# design.net
KiCad netlist of a schematic drawn in Altium Designer
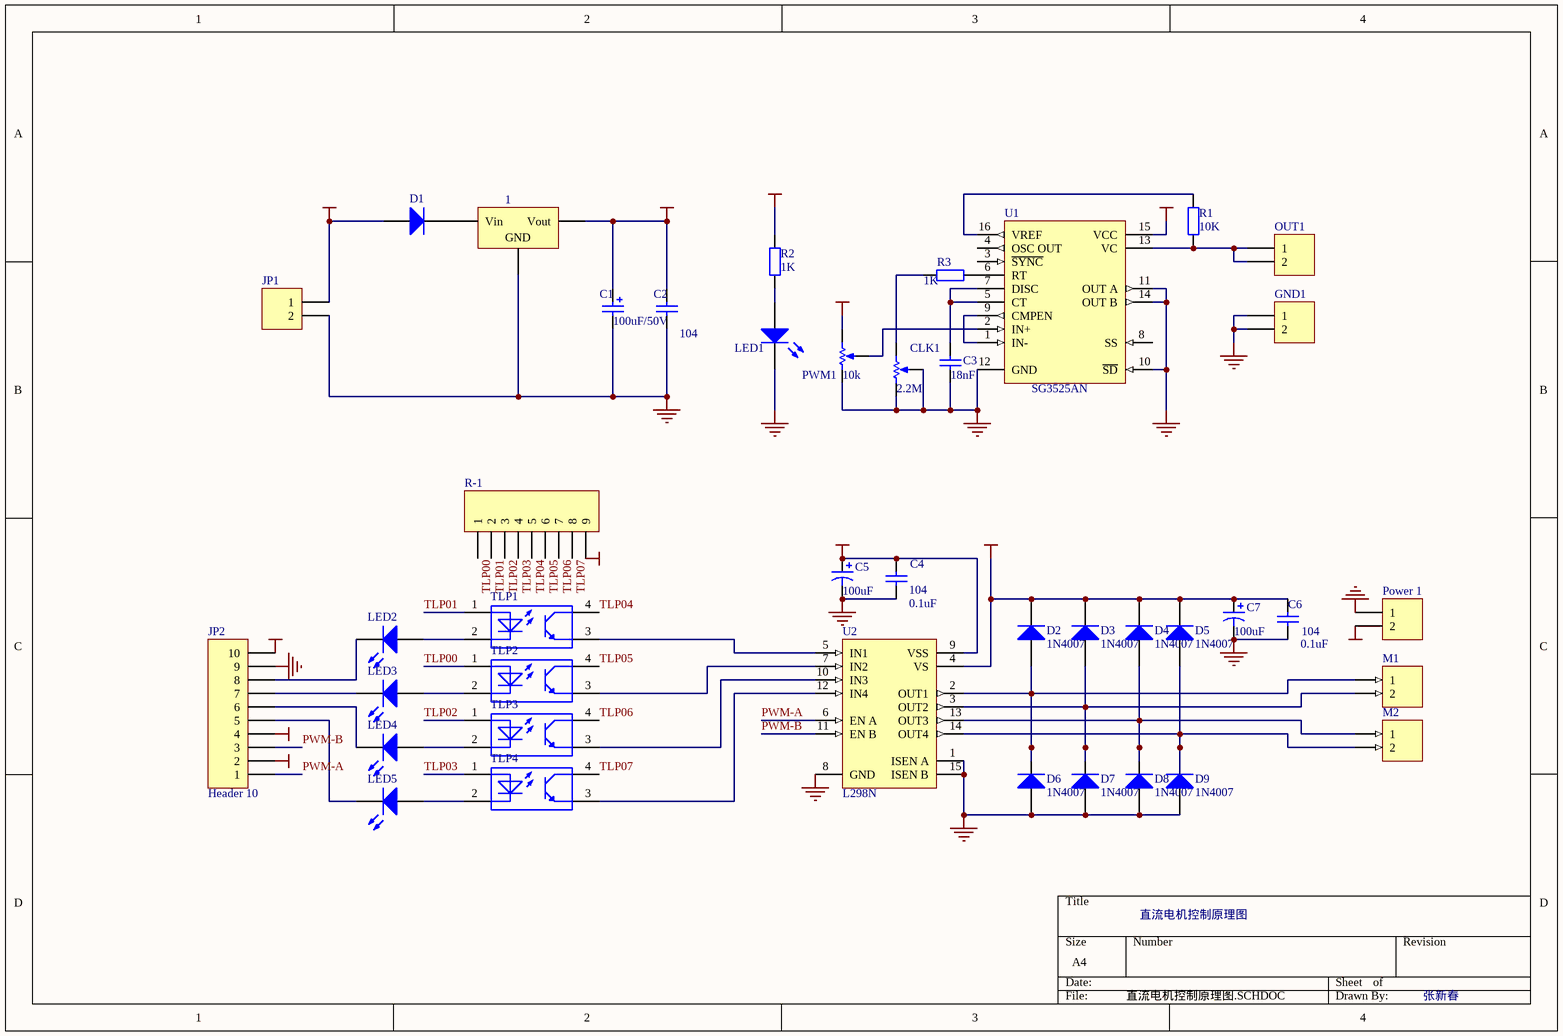
[diagram p0: 直流电机控制原理图.SCHDOC]

(export (version "E")
  (design (tool "Eeschema 10.0.6"))
  (components
    (comp (ref "1")
      (value "SDWYG")
      (footprint "WYG")
      (description "三端稳压器")
      (fields (field (name "PUBLISHER") "Altium Limited"))
      (libsource (lib "zxcourhc") (part "SDWYG"))
    )
    (comp (ref "C1")
      (value "100uF/50V")
      (footprint "C-DJ-6")
      (description "电解电容")
      (fields (field (name "Comment") "DJDR") (field (name "PUBLISHER") "Altium Limited"))
      (libsource (lib "zxcourhc") (part "DJDR"))
    )
    (comp (ref "C2")
      (value "104")
      (footprint "CPDR")
      (description "瓷片电容")
      (fields (field (name "Comment") "CPDR") (field (name "PUBLISHER") "Altium Limited"))
      (libsource (lib "zxcourhc") (part "CPDR"))
    )
    (comp (ref "C3")
      (value "18nF")
      (footprint "CPDR")
      (description "Capacitor (Semiconductor SIM Model)")
      (fields (field (name "Comment") "Cap Semi") (field (name "PUBLISHER") "Altium Limited"))
      (libsource (lib "Miscellaneous Devices") (part "Cap Semi"))
    )
    (comp (ref "C4")
      (value "104")
      (footprint "BAT-2")
      (description "Capacitor")
      (fields (field (name "ALTIUM_VALUE") "0.1uF") (field (name "PUBLISHER") "Altium Limited"))
      (libsource (lib "Miscellaneous Devices") (part "Cap"))
    )
    (comp (ref "C5")
      (value "100uF")
      (footprint "CAPPR2-5x6.8")
      (description "Polarized Capacitor (Surface Mount)")
      (fields (field (name "PUBLISHER") "Altium Limited"))
      (libsource (lib "Miscellaneous Devices") (part "Cap Pol3"))
    )
    (comp (ref "C6")
      (value "104")
      (footprint "BAT-2")
      (description "Capacitor")
      (fields (field (name "ALTIUM_VALUE") "0.1uF") (field (name "PUBLISHER") "Altium Limited"))
      (libsource (lib "Miscellaneous Devices") (part "Cap"))
    )
    (comp (ref "C7")
      (value "100uF")
      (footprint "CAPPR2-5x6.8")
      (description "Polarized Capacitor (Surface Mount)")
      (fields (field (name "PUBLISHER") "Altium Limited"))
      (libsource (lib "Miscellaneous Devices") (part "Cap Pol3"))
    )
    (comp (ref "CLK1")
      (value "2.2M")
      (footprint "SIP3-D")
      (description "Potentiometer")
      (fields (field (name "Comment") "RPot") (field (name "PUBLISHER") "Altium Limited"))
      (libsource (lib "Miscellaneous Devices") (part "RPot"))
    )
    (comp (ref "D1")
      (value "Diode 1N4007")
      (footprint "D-ZL-10")
      (description "1 Amp General Purpose Rectifier")
      (fields (field (name "PUBLISHER") "Altium Limited"))
      (libsource (lib "Miscellaneous Devices") (part "Diode 1N4007"))
    )
    (comp (ref "D2")
      (value "1N4007")
      (footprint "DIO7.8-4.6x2")
      (description "1 Amp General Purpose Rectifier")
      (fields (field (name "PUBLISHER") "Altium Limited"))
      (libsource (lib "Miscellaneous Devices") (part "Diode 1N4007"))
    )
    (comp (ref "D3")
      (value "1N4007")
      (footprint "DIO7.8-4.6x2")
      (description "1 Amp General Purpose Rectifier")
      (fields (field (name "PUBLISHER") "Altium Limited"))
      (libsource (lib "Miscellaneous Devices") (part "Diode 1N4007"))
    )
    (comp (ref "D4")
      (value "1N4007")
      (footprint "DIO7.8-4.6x2")
      (description "1 Amp General Purpose Rectifier")
      (fields (field (name "PUBLISHER") "Altium Limited"))
      (libsource (lib "Miscellaneous Devices") (part "Diode 1N4007"))
    )
    (comp (ref "D5")
      (value "1N4007")
      (footprint "DIO7.8-4.6x2")
      (description "1 Amp General Purpose Rectifier")
      (fields (field (name "PUBLISHER") "Altium Limited"))
      (libsource (lib "Miscellaneous Devices") (part "Diode 1N4007"))
    )
    (comp (ref "D6")
      (value "1N4007")
      (footprint "DIO7.8-4.6x2")
      (description "1 Amp General Purpose Rectifier")
      (fields (field (name "PUBLISHER") "Altium Limited"))
      (libsource (lib "Miscellaneous Devices") (part "Diode 1N4007"))
    )
    (comp (ref "D7")
      (value "1N4007")
      (footprint "DIO7.8-4.6x2")
      (description "1 Amp General Purpose Rectifier")
      (fields (field (name "PUBLISHER") "Altium Limited"))
      (libsource (lib "Miscellaneous Devices") (part "Diode 1N4007"))
    )
    (comp (ref "D8")
      (value "1N4007")
      (footprint "DIO7.8-4.6x2")
      (description "1 Amp General Purpose Rectifier")
      (fields (field (name "PUBLISHER") "Altium Limited"))
      (libsource (lib "Miscellaneous Devices") (part "Diode 1N4007"))
    )
    (comp (ref "D9")
      (value "1N4007")
      (footprint "DIO7.8-4.6x2")
      (description "1 Amp General Purpose Rectifier")
      (fields (field (name "PUBLISHER") "Altium Limited"))
      (libsource (lib "Miscellaneous Devices") (part "Diode 1N4007"))
    )
    (comp (ref "GND1")
      (value "Header 2")
      (footprint "HDR1X2")
      (description "Header, 2-Pin")
      (fields (field (name "PUBLISHER") "Altium Limited"))
      (libsource (lib "Miscellaneous Connectors") (part "Header 2"))
    )
    (comp (ref "JP1")
      (value "PZ_2")
      (footprint "zxcourhc:JK128_2")
      (description "排针——2")
      (fields (field (name "PUBLISHER") "Altium Limited"))
      (libsource (lib "zxcourhc") (part "PZ_2"))
    )
    (comp (ref "JP2")
      (value "Header 10")
      (footprint "HDR1X10")
      (description "Header, 10-Pin")
      (fields (field (name "PUBLISHER") "Altium Limited"))
      (libsource (lib "Miscellaneous Connectors") (part "Header 10"))
    )
    (comp (ref "LED1")
      (value "LED2")
      (footprint "LED_D")
      (description "Typical RED, GREEN, YELLOW, AMBER GaAs LED")
      (fields (field (name "PUBLISHER") "Altium Limited"))
      (libsource (lib "Miscellaneous Devices") (part "LED2"))
    )
    (comp (ref "LED2")
      (value "~")
      (footprint "HDR1X2")
      (description "Typical BLUE SiC LED")
      (fields (field (name "PUBLISHER") "Altium Limited"))
      (libsource (lib "Miscellaneous Devices") (part "LED3"))
    )
    (comp (ref "LED3")
      (value "~")
      (footprint "HDR1X2")
      (description "Typical BLUE SiC LED")
      (fields (field (name "PUBLISHER") "Altium Limited"))
      (libsource (lib "Miscellaneous Devices") (part "LED3"))
    )
    (comp (ref "LED4")
      (value "~")
      (footprint "HDR1X2")
      (description "Typical BLUE SiC LED")
      (fields (field (name "PUBLISHER") "Altium Limited"))
      (libsource (lib "Miscellaneous Devices") (part "LED3"))
    )
    (comp (ref "LED5")
      (value "~")
      (footprint "HDR1X2")
      (description "Typical BLUE SiC LED")
      (fields (field (name "PUBLISHER") "Altium Limited"))
      (libsource (lib "Miscellaneous Devices") (part "LED3"))
    )
    (comp (ref "M1")
      (value "~")
      (footprint "JK128")
      (description "Header, 2-Pin")
      (fields (field (name "PUBLISHER") "Altium Limited"))
      (libsource (lib "Miscellaneous Connectors") (part "MHDR1X2"))
    )
    (comp (ref "M2")
      (value "~")
      (footprint "JK128")
      (description "Header, 2-Pin")
      (fields (field (name "PUBLISHER") "Altium Limited"))
      (libsource (lib "Miscellaneous Connectors") (part "MHDR1X2"))
    )
    (comp (ref "OUT1")
      (value "Header 2")
      (footprint "HDR1X2")
      (description "Header, 2-Pin")
      (fields (field (name "PUBLISHER") "Altium Limited"))
      (libsource (lib "Miscellaneous Connectors") (part "Header 2"))
    )
    (comp (ref "Power 1")
      (value "~")
      (footprint "JK128")
      (description "Header, 2-Pin")
      (fields (field (name "PUBLISHER") "Altium Limited"))
      (libsource (lib "Miscellaneous Connectors") (part "MHDR1X2"))
    )
    (comp (ref "PWM1")
      (value "10k")
      (footprint "SIP3-D")
      (description "Potentiometer")
      (fields (field (name "Comment") "RPot") (field (name "PUBLISHER") "Altium Limited"))
      (libsource (lib "Miscellaneous Devices") (part "RPot"))
    )
    (comp (ref "R-1")
      (value "~")
      (footprint "HDR1X9")
      (description "Header, 9-Pin")
      (fields (field (name "PUBLISHER") "Altium Limited"))
      (libsource (lib "Miscellaneous Connectors") (part "Header 9"))
    )
    (comp (ref "R1")
      (value "10K")
      (footprint "AXIAL-0.4")
      (description "Resistor")
      (fields (field (name "Comment") "Res2") (field (name "PUBLISHER") "Altium Limited"))
      (libsource (lib "") (part "Res2_1"))
    )
    (comp (ref "R2")
      (value "1K")
      (footprint "AXIAL-0.4")
      (description "Resistor")
      (fields (field (name "Comment") "Res2") (field (name "PUBLISHER") "Altium Limited"))
      (libsource (lib "") (part "Res2_2"))
    )
    (comp (ref "R3")
      (value "1K")
      (footprint "AXIAL-0.4")
      (description "Resistor")
      (fields (field (name "Comment") "Res2") (field (name "PUBLISHER") "Altium Limited"))
      (libsource (lib "Miscellaneous Devices") (part "Res2"))
    )
    (comp (ref "TLP1") (value "~") (footprint "DIP4") (libsource (lib "MyInt_Lib") (part "TLP521-1")))
    (comp (ref "TLP2") (value "~") (footprint "DIP4") (libsource (lib "MyInt_Lib") (part "TLP521-1")))
    (comp (ref "TLP3") (value "~") (footprint "DIP4") (libsource (lib "MyInt_Lib") (part "TLP521-1")))
    (comp (ref "TLP4") (value "~") (footprint "DIP4") (libsource (lib "MyInt_Lib") (part "TLP521-1")))
    (comp (ref "U1")
      (value "SG3525AN")
      (footprint "DIP16")
      (description "Pulse Width Modulator Control Circuit")
      (fields (field (name "PUBLISHER") "Altium Limited"))
      (libsource (lib "ON Semi Power Mgt SMPS Controller") (part "SG3525AN"))
    )
    (comp (ref "U2")
      (value "L298N")
      (footprint "DFM-T15/X1.6V")
      (description "Dual Full Bridge Driver")
      (fields (field (name "PUBLISHER") "Altium Limited"))
      (libsource (lib "ST Interface DC Motor Controller") (part "L298N"))
    )
  )
  (nets
    (net (code "1") (name "+5V") (class "Default")
      (node (ref "C4") (pin "2") (pinfunction "2_2") (pintype "passive"))
      (node (ref "C5") (pin "1") (pinfunction "1_1") (pintype "passive"))
      (node (ref "JP2") (pin "10") (pinfunction "10_10") (pintype "passive"))
      (node (ref "JP2") (pin "2") (pinfunction "2_2") (pintype "passive"))
      (node (ref "JP2") (pin "4") (pinfunction "4_4") (pintype "passive"))
      (node (ref "R-1") (pin "9") (pinfunction "9_9") (pintype "passive"))
      (node (ref "U2") (pin "9") (pinfunction "VSS_9") (pintype "power_in"))
    )
    (net (code "2") (name "+12V") (class "Default")
      (node (ref "C6") (pin "2") (pinfunction "2_2") (pintype "passive"))
      (node (ref "C7") (pin "1") (pinfunction "1_1") (pintype "passive"))
      (node (ref "D2") (pin "2") (pinfunction "K_2") (pintype "passive"))
      (node (ref "D3") (pin "2") (pinfunction "K_2") (pintype "passive"))
      (node (ref "D4") (pin "2") (pinfunction "K_2") (pintype "passive"))
      (node (ref "D5") (pin "2") (pinfunction "K_2") (pintype "passive"))
      (node (ref "Power 1") (pin "2") (pinfunction "2_2") (pintype "input"))
      (node (ref "U2") (pin "4") (pinfunction "VS_4") (pintype "power_in"))
    )
    (net (code "3") (name "/PWM-A") (class "Default")
      (node (ref "JP2") (pin "1") (pinfunction "1_1") (pintype "passive"))
      (node (ref "U2") (pin "6") (pinfunction "EN_A_6") (pintype "input"))
    )
    (net (code "4") (name "/PWM-B") (class "Default")
      (node (ref "JP2") (pin "3") (pinfunction "3_3") (pintype "passive"))
      (node (ref "U2") (pin "11") (pinfunction "EN_B_11") (pintype "input"))
    )
    (net (code "5") (name "/TLP00") (class "Default")
      (node (ref "R-1") (pin "1") (pinfunction "1_1") (pintype "passive"))
      (node (ref "TLP2") (pin "1") (pinfunction "1_1") (pintype "passive"))
    )
    (net (code "6") (name "/TLP01") (class "Default")
      (node (ref "R-1") (pin "2") (pinfunction "2_2") (pintype "passive"))
      (node (ref "TLP1") (pin "1") (pinfunction "1_1") (pintype "passive"))
    )
    (net (code "7") (name "/TLP02") (class "Default")
      (node (ref "R-1") (pin "3") (pinfunction "3_3") (pintype "passive"))
      (node (ref "TLP3") (pin "1") (pinfunction "1_1") (pintype "passive"))
    )
    (net (code "8") (name "/TLP03") (class "Default")
      (node (ref "R-1") (pin "4") (pinfunction "4_4") (pintype "passive"))
      (node (ref "TLP4") (pin "1") (pinfunction "1_1") (pintype "passive"))
    )
    (net (code "9") (name "/TLP04") (class "Default")
      (node (ref "R-1") (pin "5") (pinfunction "5_5") (pintype "passive"))
      (node (ref "TLP1") (pin "4") (pinfunction "4_4") (pintype "passive"))
    )
    (net (code "10") (name "/TLP05") (class "Default")
      (node (ref "R-1") (pin "6") (pinfunction "6_6") (pintype "passive"))
      (node (ref "TLP2") (pin "4") (pinfunction "4_4") (pintype "passive"))
    )
    (net (code "11") (name "/TLP06") (class "Default")
      (node (ref "R-1") (pin "7") (pinfunction "7_7") (pintype "passive"))
      (node (ref "TLP3") (pin "4") (pinfunction "4_4") (pintype "passive"))
    )
    (net (code "12") (name "/TLP07") (class "Default")
      (node (ref "R-1") (pin "8") (pinfunction "8_8") (pintype "passive"))
      (node (ref "TLP4") (pin "4") (pinfunction "4_4") (pintype "passive"))
    )
    (net (code "13") (name "GND") (class "Default")
      (node (ref "1") (pin "3") (pinfunction "GND_3") (pintype "passive"))
      (node (ref "C1") (pin "2") (pinfunction "2_2") (pintype "passive"))
      (node (ref "C2") (pin "1") (pinfunction "1_1") (pintype "passive"))
      (node (ref "C3") (pin "2") (pinfunction "2_2") (pintype "passive"))
      (node (ref "C4") (pin "1") (pinfunction "1_1") (pintype "passive"))
      (node (ref "C5") (pin "2") (pinfunction "2_2") (pintype "passive"))
      (node (ref "CLK1") (pin "1") (pinfunction "TOP_1") (pintype "passive"))
      (node (ref "CLK1") (pin "3") (pinfunction "TAP_3") (pintype "passive"))
      (node (ref "GND1") (pin "1") (pinfunction "1_1") (pintype "passive"))
      (node (ref "GND1") (pin "2") (pinfunction "2_2") (pintype "passive"))
      (node (ref "JP1") (pin "2") (pinfunction "2_2") (pintype "passive"))
      (node (ref "JP2") (pin "9") (pinfunction "9_9") (pintype "passive"))
      (node (ref "LED1") (pin "2") (pinfunction "K_2") (pintype "passive"))
      (node (ref "PWM1") (pin "1") (pinfunction "TOP_1") (pintype "passive"))
      (node (ref "U1") (pin "10") (pinfunction "~{SD}_10") (pintype "input"))
      (node (ref "U1") (pin "11") (pinfunction "OUT_A_11") (pintype "output"))
      (node (ref "U1") (pin "12") (pinfunction "GND_12") (pintype "power_in"))
      (node (ref "U1") (pin "14") (pinfunction "OUT_B_14") (pintype "output"))
      (node (ref "U2") (pin "8") (pinfunction "GND_8") (pintype "power_in"))
    )
    (net (code "14") (name "GND-12") (class "Default")
      (node (ref "C6") (pin "1") (pinfunction "1_1") (pintype "passive"))
      (node (ref "C7") (pin "2") (pinfunction "2_2") (pintype "passive"))
      (node (ref "D6") (pin "1") (pinfunction "A_1") (pintype "passive"))
      (node (ref "D7") (pin "1") (pinfunction "A_1") (pintype "passive"))
      (node (ref "D8") (pin "1") (pinfunction "A_1") (pintype "passive"))
      (node (ref "D9") (pin "1") (pinfunction "A_1") (pintype "passive"))
      (node (ref "Power 1") (pin "1") (pinfunction "1_1") (pintype "input"))
      (node (ref "U2") (pin "1") (pinfunction "ISEN_A_1") (pintype "passive"))
      (node (ref "U2") (pin "15") (pinfunction "ISEN_B_15") (pintype "passive"))
    )
    (net (code "15") (name "Net-(1-Vin)") (class "Default")
      (node (ref "1") (pin "1") (pinfunction "Vin_1") (pintype "passive"))
      (node (ref "D1") (pin "2") (pinfunction "K_2") (pintype "passive"))
    )
    (net (code "16") (name "Net-(CLK1-BOT)") (class "Default")
      (node (ref "CLK1") (pin "2") (pinfunction "BOT_2") (pintype "passive"))
      (node (ref "R3") (pin "2") (pinfunction "2_2") (pintype "passive"))
    )
    (net (code "17") (name "Net-(D2-A)") (class "Default")
      (node (ref "D2") (pin "1") (pinfunction "A_1") (pintype "passive"))
      (node (ref "D6") (pin "2") (pinfunction "K_2") (pintype "passive"))
      (node (ref "M1") (pin "1") (pinfunction "1_1") (pintype "input"))
      (node (ref "U2") (pin "2") (pinfunction "OUT1_2") (pintype "output"))
    )
    (net (code "18") (name "Net-(D3-A)") (class "Default")
      (node (ref "D3") (pin "1") (pinfunction "A_1") (pintype "passive"))
      (node (ref "D7") (pin "2") (pinfunction "K_2") (pintype "passive"))
      (node (ref "M1") (pin "2") (pinfunction "2_2") (pintype "input"))
      (node (ref "U2") (pin "3") (pinfunction "OUT2_3") (pintype "output"))
    )
    (net (code "19") (name "Net-(D4-A)") (class "Default")
      (node (ref "D4") (pin "1") (pinfunction "A_1") (pintype "passive"))
      (node (ref "D8") (pin "2") (pinfunction "K_2") (pintype "passive"))
      (node (ref "M2") (pin "1") (pinfunction "1_1") (pintype "input"))
      (node (ref "U2") (pin "13") (pinfunction "OUT3_13") (pintype "output"))
    )
    (net (code "20") (name "Net-(D5-A)") (class "Default")
      (node (ref "D5") (pin "1") (pinfunction "A_1") (pintype "passive"))
      (node (ref "D9") (pin "2") (pinfunction "K_2") (pintype "passive"))
      (node (ref "M2") (pin "2") (pinfunction "2_2") (pintype "input"))
      (node (ref "U2") (pin "14") (pinfunction "OUT4_14") (pintype "output"))
    )
    (net (code "21") (name "Net-(LED1-A)") (class "Default")
      (node (ref "LED1") (pin "1") (pinfunction "A_1") (pintype "passive"))
      (node (ref "R2") (pin "2") (pinfunction "2_2") (pintype "passive"))
    )
    (net (code "22") (name "Net-(LED2-A)") (class "Default")
      (node (ref "LED2") (pin "1") (pinfunction "A_1") (pintype "passive"))
      (node (ref "TLP1") (pin "2") (pinfunction "2_2") (pintype "passive"))
    )
    (net (code "23") (name "Net-(LED2-K)") (class "Default")
      (node (ref "JP2") (pin "8") (pinfunction "8_8") (pintype "passive"))
      (node (ref "LED2") (pin "2") (pinfunction "K_2") (pintype "passive"))
    )
    (net (code "24") (name "Net-(LED3-A)") (class "Default")
      (node (ref "LED3") (pin "1") (pinfunction "A_1") (pintype "passive"))
      (node (ref "TLP2") (pin "2") (pinfunction "2_2") (pintype "passive"))
    )
    (net (code "25") (name "Net-(LED3-K)") (class "Default")
      (node (ref "JP2") (pin "7") (pinfunction "7_7") (pintype "passive"))
      (node (ref "LED3") (pin "2") (pinfunction "K_2") (pintype "passive"))
    )
    (net (code "26") (name "Net-(LED4-A)") (class "Default")
      (node (ref "LED4") (pin "1") (pinfunction "A_1") (pintype "passive"))
      (node (ref "TLP3") (pin "2") (pinfunction "2_2") (pintype "passive"))
    )
    (net (code "27") (name "Net-(LED4-K)") (class "Default")
      (node (ref "JP2") (pin "6") (pinfunction "6_6") (pintype "passive"))
      (node (ref "LED4") (pin "2") (pinfunction "K_2") (pintype "passive"))
    )
    (net (code "28") (name "Net-(LED5-A)") (class "Default")
      (node (ref "LED5") (pin "1") (pinfunction "A_1") (pintype "passive"))
      (node (ref "TLP4") (pin "2") (pinfunction "2_2") (pintype "passive"))
    )
    (net (code "29") (name "Net-(LED5-K)") (class "Default")
      (node (ref "JP2") (pin "5") (pinfunction "5_5") (pintype "passive"))
      (node (ref "LED5") (pin "2") (pinfunction "K_2") (pintype "passive"))
    )
    (net (code "30") (name "Net-(PWM1-TAP)") (class "Default")
      (node (ref "PWM1") (pin "3") (pinfunction "TAP_3") (pintype "passive"))
      (node (ref "U1") (pin "2") (pinfunction "IN+_2") (pintype "input"))
    )
    (net (code "31") (name "Net-(U1-CMPEN)") (class "Default")
      (node (ref "U1") (pin "1") (pinfunction "IN-_1") (pintype "input"))
      (node (ref "U1") (pin "9") (pinfunction "CMPEN_9") (pintype "output"))
    )
    (net (code "32") (name "Net-(U1-CT)") (class "Default")
      (node (ref "C3") (pin "1") (pinfunction "1_1") (pintype "passive"))
      (node (ref "U1") (pin "5") (pinfunction "CT_5") (pintype "passive"))
      (node (ref "U1") (pin "7") (pinfunction "DISC_7") (pintype "open_collector"))
    )
    (net (code "33") (name "Net-(U1-RT)") (class "Default")
      (node (ref "R3") (pin "1") (pinfunction "1_1") (pintype "passive"))
      (node (ref "U1") (pin "6") (pinfunction "RT_6") (pintype "passive"))
    )
    (net (code "34") (name "Net-(U1-VC)") (class "Default")
      (node (ref "OUT1") (pin "1") (pinfunction "1_1") (pintype "passive"))
      (node (ref "OUT1") (pin "2") (pinfunction "2_2") (pintype "passive"))
      (node (ref "R1") (pin "1") (pinfunction "1_1") (pintype "passive"))
      (node (ref "U1") (pin "13") (pinfunction "VC_13") (pintype "power_in"))
    )
    (net (code "35") (name "Net-(U1-VREF)") (class "Default")
      (node (ref "R1") (pin "2") (pinfunction "2_2") (pintype "passive"))
      (node (ref "U1") (pin "16") (pinfunction "VREF_16") (pintype "output"))
    )
    (net (code "36") (name "Net-(U2-IN1)") (class "Default")
      (node (ref "TLP1") (pin "3") (pinfunction "3_3") (pintype "passive"))
      (node (ref "U2") (pin "5") (pinfunction "IN1_5") (pintype "input"))
    )
    (net (code "37") (name "Net-(U2-IN2)") (class "Default")
      (node (ref "TLP2") (pin "3") (pinfunction "3_3") (pintype "passive"))
      (node (ref "U2") (pin "7") (pinfunction "IN2_7") (pintype "input"))
    )
    (net (code "38") (name "Net-(U2-IN3)") (class "Default")
      (node (ref "TLP3") (pin "3") (pinfunction "3_3") (pintype "passive"))
      (node (ref "U2") (pin "10") (pinfunction "IN3_10") (pintype "input"))
    )
    (net (code "39") (name "Net-(U2-IN4)") (class "Default")
      (node (ref "TLP4") (pin "3") (pinfunction "3_3") (pintype "passive"))
      (node (ref "U2") (pin "12") (pinfunction "IN4_12") (pintype "input"))
    )
    (net (code "40") (name "VCC1") (class "Default")
      (node (ref "D1") (pin "1") (pinfunction "A_1") (pintype "passive"))
      (node (ref "JP1") (pin "1") (pinfunction "1_1") (pintype "passive"))
      (node (ref "U1") (pin "15") (pinfunction "VCC_15") (pintype "power_in"))
    )
    (net (code "41") (name "VCC2") (class "Default")
      (node (ref "1") (pin "2") (pinfunction "Vout_2") (pintype "passive"))
      (node (ref "C1") (pin "1") (pinfunction "1_1") (pintype "passive"))
      (node (ref "C2") (pin "2") (pinfunction "2_2") (pintype "passive"))
      (node (ref "PWM1") (pin "2") (pinfunction "BOT_2") (pintype "passive"))
      (node (ref "R2") (pin "1") (pinfunction "1_1") (pintype "passive"))
    )
    (net (code "42") (name "unconnected-(U1-OSC_OUT-Pad4)") (class "Default")
      (node (ref "U1") (pin "4") (pinfunction "OSC_OUT_4") (pintype "output"))
    )
    (net (code "43") (name "unconnected-(U1-SS-Pad8)") (class "Default")
      (node (ref "U1") (pin "8") (pinfunction "SS_8") (pintype "input"))
    )
    (net (code "44") (name "unconnected-(U1-~{SYNC}-Pad3)") (class "Default")
      (node (ref "U1") (pin "3") (pinfunction "~{SYNC}_3") (pintype "input"))
    )
  )
)
